# Contatore_a_relay_2bit_-_Product.net
KiCad netlist of a schematic drawn in EAGLE
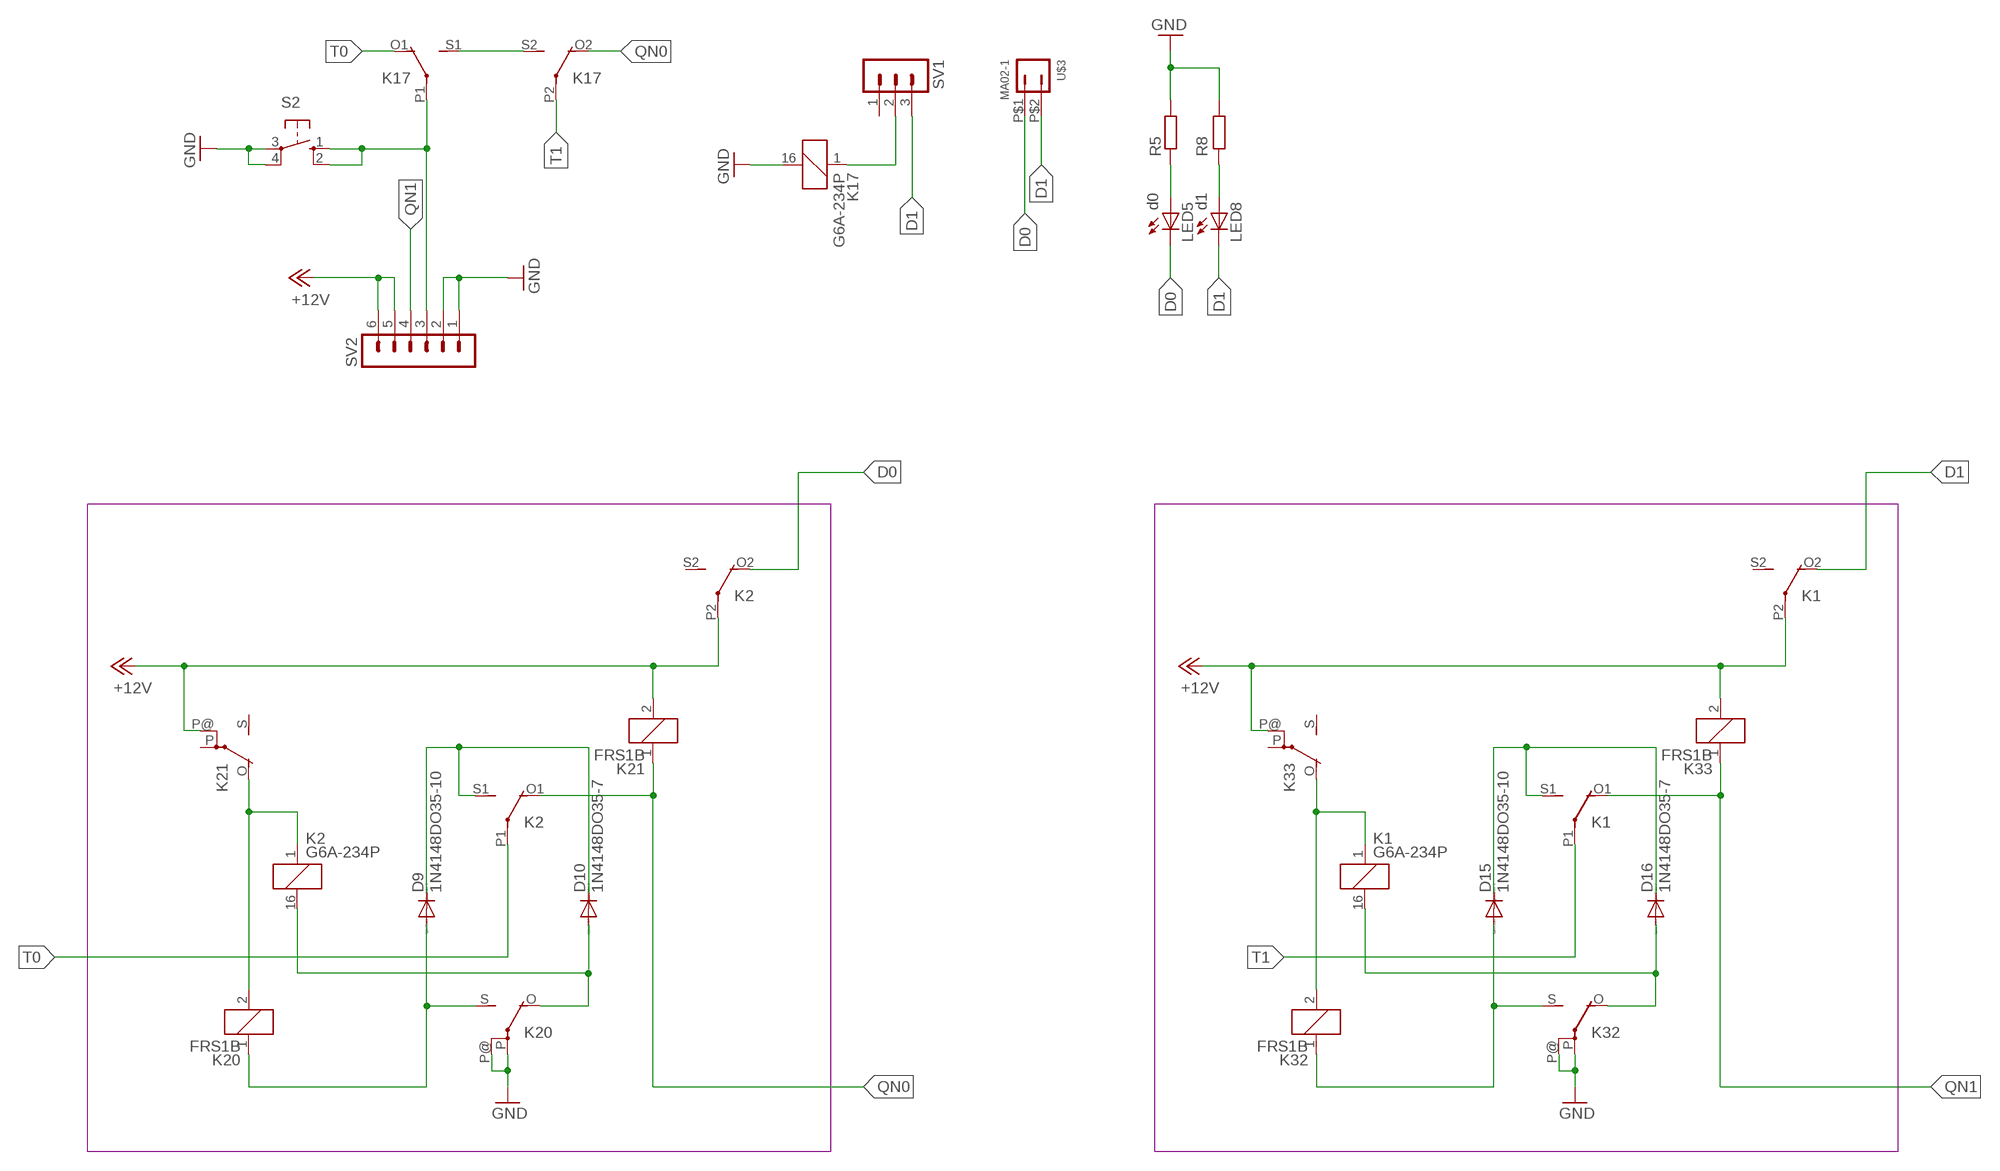
[diagram p0: schematic, sheet 1]

(export (version "E")
  (design (tool "Eeschema 10.0.6"))
  (components
    (comp (ref "D9")
      (value "1N4148DO35-10")
      (footprint "eagle-import:DO35-10")
      (libsource (lib "eagle-import") (part "1N4148DO35-10"))
    )
    (comp (ref "D10")
      (value "1N4148DO35-7")
      (footprint "eagle-import:DO35-7")
      (libsource (lib "eagle-import") (part "1N4148DO35-7"))
    )
    (comp (ref "D15")
      (value "1N4148DO35-10")
      (footprint "eagle-import:DO35-10")
      (libsource (lib "eagle-import") (part "1N4148DO35-10"))
    )
    (comp (ref "D16")
      (value "1N4148DO35-7")
      (footprint "eagle-import:DO35-7")
      (libsource (lib "eagle-import") (part "1N4148DO35-7"))
    )
    (comp (ref "K1")
      (value "G6A-234P")
      (footprint "eagle-import:G6A-234P")
      (libsource (lib "eagle-import") (part "G6A-234P"))
    )
    (comp (ref "K2")
      (value "G6A-234P")
      (footprint "eagle-import:G6A-234P")
      (libsource (lib "eagle-import") (part "G6A-234P"))
    )
    (comp (ref "K17")
      (value "G6A-234P")
      (footprint "eagle-import:G6A-234P")
      (libsource (lib "eagle-import") (part "G6A-234P"))
    )
    (comp (ref "K20")
      (value "FRS1B")
      (footprint "eagle-import:FRS1B")
      (libsource (lib "eagle-import") (part "FRS1B"))
    )
    (comp (ref "K21")
      (value "FRS1B")
      (footprint "eagle-import:FRS1B")
      (libsource (lib "eagle-import") (part "FRS1B"))
    )
    (comp (ref "K32")
      (value "FRS1B")
      (footprint "eagle-import:FRS1B")
      (libsource (lib "eagle-import") (part "FRS1B"))
    )
    (comp (ref "K33")
      (value "FRS1B")
      (footprint "eagle-import:FRS1B")
      (libsource (lib "eagle-import") (part "FRS1B"))
    )
    (comp (ref "LED5")
      (value "d0")
      (footprint "eagle-import:LED3MM")
      (libsource (lib "eagle-import") (part "LED3MM"))
    )
    (comp (ref "LED8")
      (value "d1")
      (footprint "eagle-import:LED3MM")
      (libsource (lib "eagle-import") (part "LED3MM"))
    )
    (comp (ref "R5")
      (value "R-EU_M0805")
      (footprint "eagle-import:M0805")
      (libsource (lib "eagle-import") (part "R-EU_M0805"))
    )
    (comp (ref "R8")
      (value "R-EU_M0805")
      (footprint "eagle-import:M0805")
      (libsource (lib "eagle-import") (part "R-EU_M0805"))
    )
    (comp (ref "S2")
      (value "10-XX")
      (footprint "eagle-import:B3F-10XX")
      (fields (field (name "MPN") "B3F-1000"))
      (libsource (lib "eagle-import") (part "10-XX"))
    )
    (comp (ref "SV1")
      (value "MA03-1")
      (footprint "eagle-import:MA03-1")
      (libsource (lib "eagle-import") (part "MA03-1"))
    )
    (comp (ref "SV2")
      (value "MA06-1")
      (footprint "eagle-import:MA06-1")
      (libsource (lib "eagle-import") (part "MA06-1"))
    )
    (comp (ref "U$3")
      (value "MA02-1")
      (footprint "eagle-import:MA02-1")
      (libsource (lib "eagle-import") (part "MA02-1"))
    )
  )
  (nets
    (net (code "1") (name "+12V") (class "Default")
      (node (ref "K1") (pin "P2") (pinfunction "P_P2") (pintype "passive"))
      (node (ref "K2") (pin "P2") (pinfunction "P_P2") (pintype "passive"))
      (node (ref "K21") (pin "2") (pinfunction "2_2") (pintype "passive"))
      (node (ref "K21") (pin "P@") (pinfunction "P_P@") (pintype "passive"))
      (node (ref "K33") (pin "2") (pinfunction "2_2") (pintype "passive"))
      (node (ref "K33") (pin "P@") (pinfunction "P_P@") (pintype "passive"))
      (node (ref "SV2") (pin "5") (pinfunction "5_5") (pintype "passive"))
      (node (ref "SV2") (pin "6") (pinfunction "6_6") (pintype "passive"))
    )
    (net (code "2") (name "D0") (class "Default")
      (node (ref "K2") (pin "O2") (pinfunction "O_O2") (pintype "passive"))
      (node (ref "LED5") (pin "K") (pinfunction "C_K") (pintype "passive"))
      (node (ref "U$3") (pin "P$1") (pinfunction "1_P$1") (pintype "passive"))
    )
    (net (code "3") (name "D1") (class "Default")
      (node (ref "K1") (pin "O2") (pinfunction "O_O2") (pintype "passive"))
      (node (ref "LED8") (pin "K") (pinfunction "C_K") (pintype "passive"))
      (node (ref "SV1") (pin "3") (pinfunction "3_3") (pintype "passive"))
      (node (ref "U$3") (pin "P$2") (pinfunction "2_P$2") (pintype "passive"))
    )
    (net (code "4") (name "GND") (class "Default")
      (node (ref "K17") (pin "16") (pinfunction "2_16") (pintype "passive"))
      (node (ref "K20") (pin "P") (pinfunction "P_P") (pintype "passive"))
      (node (ref "K20") (pin "P@") (pinfunction "P_P@") (pintype "passive"))
      (node (ref "K32") (pin "P") (pinfunction "P_P") (pintype "passive"))
      (node (ref "K32") (pin "P@") (pinfunction "P_P@") (pintype "passive"))
      (node (ref "R5") (pin "2") (pinfunction "2_2") (pintype "passive"))
      (node (ref "R8") (pin "2") (pinfunction "2_2") (pintype "passive"))
      (node (ref "S2") (pin "3") (pinfunction "P_3") (pintype "passive"))
      (node (ref "S2") (pin "4") (pinfunction "P1_4") (pintype "passive"))
      (node (ref "SV2") (pin "1") (pinfunction "1_1") (pintype "passive"))
      (node (ref "SV2") (pin "2") (pinfunction "2_2") (pintype "passive"))
    )
    (net (code "5") (name "Net-(D9-PadA)") (class "Default")
      (node (ref "D9") (pin "A") (pinfunction "A_A") (pintype "passive"))
      (node (ref "K20") (pin "1") (pinfunction "1_1") (pintype "passive"))
      (node (ref "K20") (pin "S") (pinfunction "S_S") (pintype "passive"))
    )
    (net (code "6") (name "Net-(D15-PadA)") (class "Default")
      (node (ref "D15") (pin "A") (pinfunction "A_A") (pintype "passive"))
      (node (ref "K32") (pin "1") (pinfunction "1_1") (pintype "passive"))
      (node (ref "K32") (pin "S") (pinfunction "S_S") (pintype "passive"))
    )
    (net (code "7") (name "Net-(K1-Pad1)") (class "Default")
      (node (ref "K1") (pin "1") (pinfunction "1_1") (pintype "passive"))
      (node (ref "K32") (pin "2") (pinfunction "2_2") (pintype "passive"))
      (node (ref "K33") (pin "O") (pinfunction "O_O") (pintype "passive"))
    )
    (net (code "8") (name "Net-(K1A-2)") (class "Default")
      (node (ref "D16") (pin "A") (pinfunction "A_A") (pintype "passive"))
      (node (ref "K1") (pin "16") (pinfunction "2_16") (pintype "passive"))
      (node (ref "K32") (pin "O") (pinfunction "O_O") (pintype "passive"))
    )
    (net (code "9") (name "Net-(K1B-S)") (class "Default")
      (node (ref "D15") (pin "C") (pinfunction "C_C") (pintype "passive"))
      (node (ref "D16") (pin "C") (pinfunction "C_C") (pintype "passive"))
      (node (ref "K1") (pin "S1") (pinfunction "S_S1") (pintype "passive"))
    )
    (net (code "10") (name "Net-(K2-Pad1)") (class "Default")
      (node (ref "K2") (pin "1") (pinfunction "1_1") (pintype "passive"))
      (node (ref "K20") (pin "2") (pinfunction "2_2") (pintype "passive"))
      (node (ref "K21") (pin "O") (pinfunction "O_O") (pintype "passive"))
    )
    (net (code "11") (name "Net-(K2A-2)") (class "Default")
      (node (ref "D10") (pin "A") (pinfunction "A_A") (pintype "passive"))
      (node (ref "K2") (pin "16") (pinfunction "2_16") (pintype "passive"))
      (node (ref "K20") (pin "O") (pinfunction "O_O") (pintype "passive"))
    )
    (net (code "12") (name "Net-(K2B-S)") (class "Default")
      (node (ref "D10") (pin "C") (pinfunction "C_C") (pintype "passive"))
      (node (ref "D9") (pin "C") (pinfunction "C_C") (pintype "passive"))
      (node (ref "K2") (pin "S1") (pinfunction "S_S1") (pintype "passive"))
    )
    (net (code "13") (name "Net-(K17-Pad1)") (class "Default")
      (node (ref "K17") (pin "1") (pinfunction "1_1") (pintype "passive"))
      (node (ref "SV1") (pin "2") (pinfunction "2_2") (pintype "passive"))
    )
    (net (code "14") (name "Net-(K17B-P)") (class "Default")
      (node (ref "K17") (pin "P1") (pinfunction "P_P1") (pintype "passive"))
      (node (ref "S2") (pin "1") (pinfunction "S_1") (pintype "passive"))
      (node (ref "S2") (pin "2") (pinfunction "S1_2") (pintype "passive"))
      (node (ref "SV2") (pin "3") (pinfunction "3_3") (pintype "passive"))
    )
    (net (code "15") (name "Net-(K17B-S)") (class "Default")
      (node (ref "K17") (pin "S1") (pinfunction "S_S1") (pintype "passive"))
      (node (ref "K17") (pin "S2") (pinfunction "S_S2") (pintype "passive"))
    )
    (net (code "16") (name "Net-(LED5-PadA)") (class "Default")
      (node (ref "LED5") (pin "A") (pinfunction "A_A") (pintype "passive"))
      (node (ref "R5") (pin "1") (pinfunction "1_1") (pintype "passive"))
    )
    (net (code "17") (name "Net-(LED8-PadA)") (class "Default")
      (node (ref "LED8") (pin "A") (pinfunction "A_A") (pintype "passive"))
      (node (ref "R8") (pin "1") (pinfunction "1_1") (pintype "passive"))
    )
    (net (code "18") (name "QN0") (class "Default")
      (node (ref "K17") (pin "O2") (pinfunction "O_O2") (pintype "passive"))
      (node (ref "K2") (pin "O1") (pinfunction "O_O1") (pintype "passive"))
      (node (ref "K21") (pin "1") (pinfunction "1_1") (pintype "passive"))
    )
    (net (code "19") (name "QN1") (class "Default")
      (node (ref "K1") (pin "O1") (pinfunction "O_O1") (pintype "passive"))
      (node (ref "K33") (pin "1") (pinfunction "1_1") (pintype "passive"))
      (node (ref "SV2") (pin "4") (pinfunction "4_4") (pintype "passive"))
    )
    (net (code "20") (name "T0") (class "Default")
      (node (ref "K17") (pin "O1") (pinfunction "O_O1") (pintype "passive"))
      (node (ref "K2") (pin "P1") (pinfunction "P_P1") (pintype "passive"))
    )
    (net (code "21") (name "T1") (class "Default")
      (node (ref "K1") (pin "P1") (pinfunction "P_P1") (pintype "passive"))
      (node (ref "K17") (pin "P2") (pinfunction "P_P2") (pintype "passive"))
    )
    (net (code "22") (name "unconnected-(K1C-S-PadS2)") (class "Default")
      (node (ref "K1") (pin "S2") (pinfunction "S_S2") (pintype "passive"))
    )
    (net (code "23") (name "unconnected-(K2C-S-PadS2)") (class "Default")
      (node (ref "K2") (pin "S2") (pinfunction "S_S2") (pintype "passive"))
    )
    (net (code "24") (name "unconnected-(K21-PadP)") (class "Default")
      (node (ref "K21") (pin "P") (pinfunction "P_P") (pintype "passive"))
    )
    (net (code "25") (name "unconnected-(K21-PadS)") (class "Default")
      (node (ref "K21") (pin "S") (pinfunction "S_S") (pintype "passive"))
    )
    (net (code "26") (name "unconnected-(K33-PadP)") (class "Default")
      (node (ref "K33") (pin "P") (pinfunction "P_P") (pintype "passive"))
    )
    (net (code "27") (name "unconnected-(K33-PadS)") (class "Default")
      (node (ref "K33") (pin "S") (pinfunction "S_S") (pintype "passive"))
    )
    (net (code "28") (name "unconnected-(SV1-Pad1)") (class "Default")
      (node (ref "SV1") (pin "1") (pinfunction "1_1") (pintype "passive"))
    )
  )
)
